# Firefly.net
KiCad netlist of a schematic drawn in EAGLE
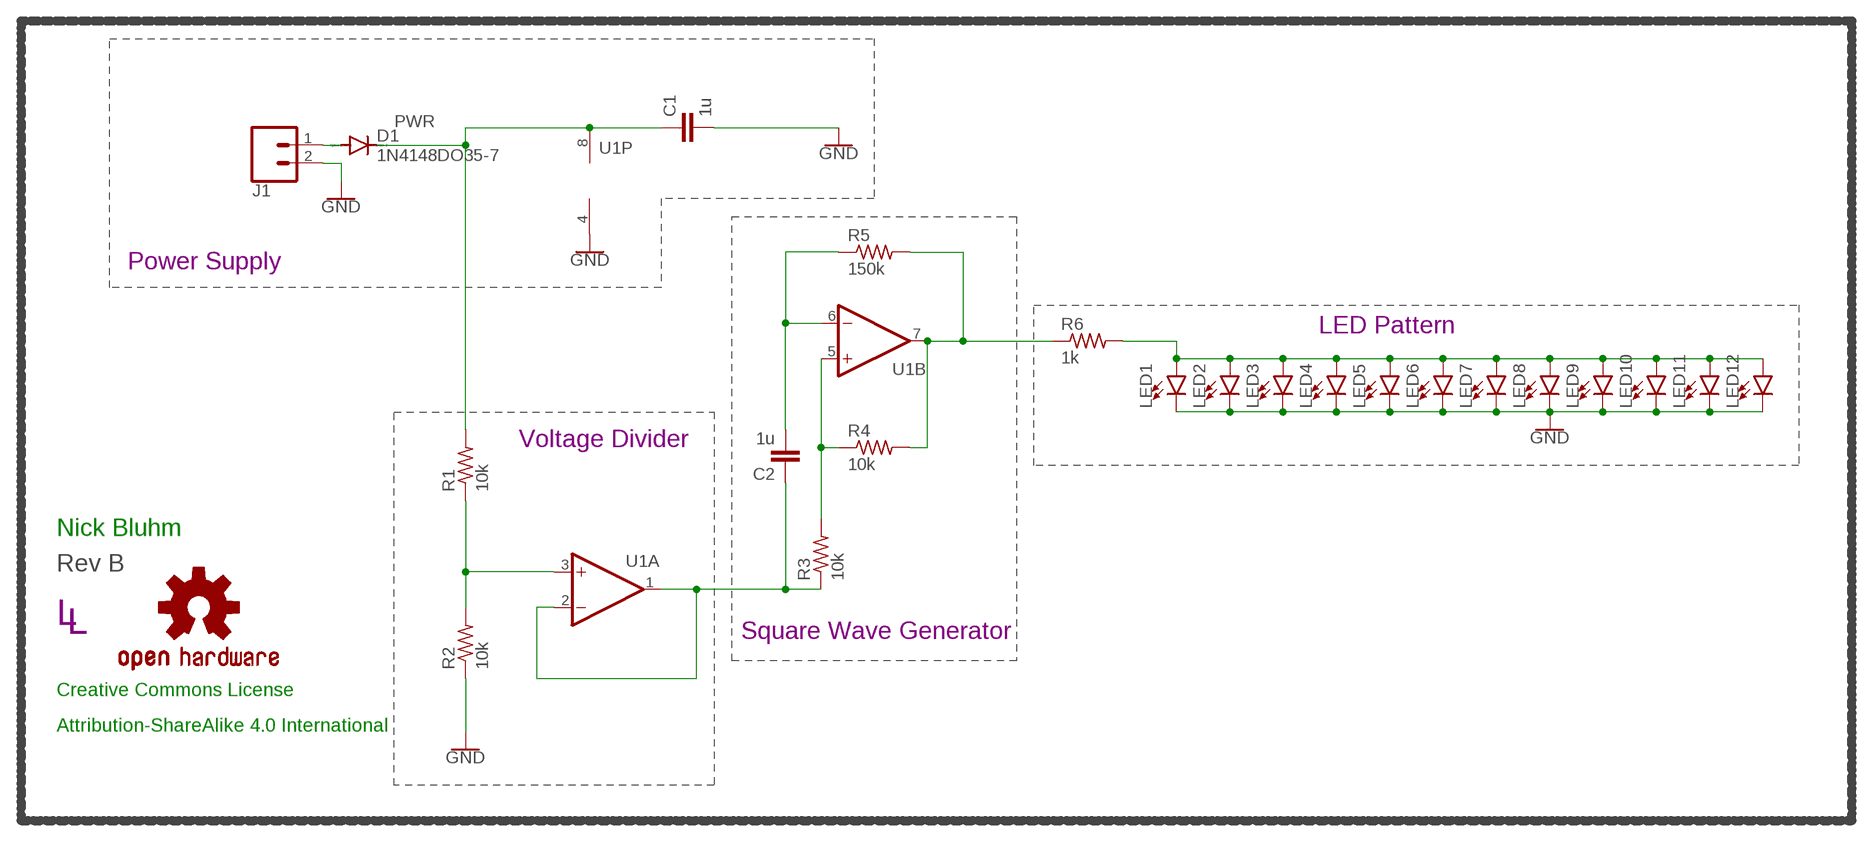
[diagram p0: schematic, sheet 1]

(export (version "E")
  (design (tool "Eeschema 10.0.6"))
  (components
    (comp (ref "C1")
      (value "1u")
      (footprint "eagle-import:C0805")
      (libsource (lib "eagle-import") (part "CAPACITOR0805"))
    )
    (comp (ref "C2")
      (value "1u")
      (footprint "eagle-import:C0805")
      (libsource (lib "eagle-import") (part "CAPACITOR0805"))
    )
    (comp (ref "D1")
      (value "1N4148DO35-7")
      (footprint "eagle-import:DO35-7")
      (libsource (lib "eagle-import") (part "1N4148DO35-7"))
    )
    (comp (ref "J1")
      (value "CONN_02")
      (footprint "eagle-import:1X02")
      (libsource (lib "eagle-import") (part "CONN_02"))
    )
    (comp (ref "LED1")
      (value "LED5MM")
      (footprint "eagle-import:LED_5MM")
      (libsource (lib "eagle-import") (part "LED5MM"))
    )
    (comp (ref "LED2")
      (value "LED5MM")
      (footprint "eagle-import:LED_5MM")
      (libsource (lib "eagle-import") (part "LED5MM"))
    )
    (comp (ref "LED3")
      (value "LED5MM")
      (footprint "eagle-import:LED_5MM")
      (libsource (lib "eagle-import") (part "LED5MM"))
    )
    (comp (ref "LED4")
      (value "LED5MM")
      (footprint "eagle-import:LED_5MM")
      (libsource (lib "eagle-import") (part "LED5MM"))
    )
    (comp (ref "LED5")
      (value "LED5MM")
      (footprint "eagle-import:LED_5MM")
      (libsource (lib "eagle-import") (part "LED5MM"))
    )
    (comp (ref "LED6")
      (value "LED5MM")
      (footprint "eagle-import:LED_5MM")
      (libsource (lib "eagle-import") (part "LED5MM"))
    )
    (comp (ref "LED7")
      (value "LED5MM")
      (footprint "eagle-import:LED_5MM")
      (libsource (lib "eagle-import") (part "LED5MM"))
    )
    (comp (ref "LED8")
      (value "LED5MM")
      (footprint "eagle-import:LED_5MM")
      (libsource (lib "eagle-import") (part "LED5MM"))
    )
    (comp (ref "LED9")
      (value "LED5MM")
      (footprint "eagle-import:LED_5MM")
      (libsource (lib "eagle-import") (part "LED5MM"))
    )
    (comp (ref "LED10")
      (value "LED5MM")
      (footprint "eagle-import:LED_5MM")
      (libsource (lib "eagle-import") (part "LED5MM"))
    )
    (comp (ref "LED11")
      (value "LED5MM")
      (footprint "eagle-import:LED_5MM")
      (libsource (lib "eagle-import") (part "LED5MM"))
    )
    (comp (ref "LED12")
      (value "LED5MM")
      (footprint "eagle-import:LED_5MM")
      (libsource (lib "eagle-import") (part "LED5MM"))
    )
    (comp (ref "LOGO1")
      (value "OSHW-LOGOL")
      (footprint "eagle-import:OSHW-LOGO-L")
      (libsource (lib "eagle-import") (part "OSHW-LOGOL"))
    )
    (comp (ref "R1")
      (value "10k")
      (footprint "eagle-import:R0805")
      (libsource (lib "eagle-import") (part "RESISTOR0805"))
    )
    (comp (ref "R2")
      (value "10k")
      (footprint "eagle-import:R0805")
      (libsource (lib "eagle-import") (part "RESISTOR0805"))
    )
    (comp (ref "R3")
      (value "10k")
      (footprint "eagle-import:R0805")
      (libsource (lib "eagle-import") (part "RESISTOR0805"))
    )
    (comp (ref "R4")
      (value "10k")
      (footprint "eagle-import:R0805")
      (libsource (lib "eagle-import") (part "RESISTOR0805"))
    )
    (comp (ref "R5")
      (value "150k")
      (footprint "eagle-import:R0805")
      (libsource (lib "eagle-import") (part "RESISTOR0805"))
    )
    (comp (ref "R6")
      (value "1k")
      (footprint "eagle-import:R0805")
      (libsource (lib "eagle-import") (part "RESISTOR0805"))
    )
    (comp (ref "U$4")
      (value "REVISION.B")
      (footprint "eagle-import:REV.B")
      (libsource (lib "eagle-import") (part "REVISION.B"))
    )
    (comp (ref "U$5")
      (value "LINNES.LAB.LOGO")
      (footprint "eagle-import:LINNES.LAB.LOGO")
      (libsource (lib "eagle-import") (part "LINNES.LAB.LOGO"))
    )
    (comp (ref "U1")
      (value "OP-DUALMCP6002R")
      (footprint "eagle-import:SO8")
      (fields (field (name "MF") "Microchip Technology") (field (name "MPN") "MCP6002T-I/SN"))
      (libsource (lib "eagle-import") (part "OP-DUALRMCP6002"))
    )
  )
  (nets
    (net (code "1") (name "/PWR") (class "Default")
      (node (ref "C1") (pin "1") (pinfunction "1_1") (pintype "passive"))
      (node (ref "D1") (pin "C") (pinfunction "C_C") (pintype "passive"))
      (node (ref "R1") (pin "2") (pinfunction "2_2") (pintype "passive"))
      (node (ref "U1") (pin "8") (pinfunction "V+_8") (pintype "power_in"))
    )
    (net (code "2") (name "GND") (class "Default")
      (node (ref "C1") (pin "2") (pinfunction "2_2") (pintype "passive"))
      (node (ref "J1") (pin "2") (pinfunction "2_2") (pintype "passive"))
      (node (ref "LED1") (pin "K") (pinfunction "C_K") (pintype "passive"))
      (node (ref "LED10") (pin "K") (pinfunction "C_K") (pintype "passive"))
      (node (ref "LED11") (pin "K") (pinfunction "C_K") (pintype "passive"))
      (node (ref "LED12") (pin "K") (pinfunction "C_K") (pintype "passive"))
      (node (ref "LED2") (pin "K") (pinfunction "C_K") (pintype "passive"))
      (node (ref "LED3") (pin "K") (pinfunction "C_K") (pintype "passive"))
      (node (ref "LED4") (pin "K") (pinfunction "C_K") (pintype "passive"))
      (node (ref "LED5") (pin "K") (pinfunction "C_K") (pintype "passive"))
      (node (ref "LED6") (pin "K") (pinfunction "C_K") (pintype "passive"))
      (node (ref "LED7") (pin "K") (pinfunction "C_K") (pintype "passive"))
      (node (ref "LED8") (pin "K") (pinfunction "C_K") (pintype "passive"))
      (node (ref "LED9") (pin "K") (pinfunction "C_K") (pintype "passive"))
      (node (ref "R2") (pin "1") (pinfunction "1_1") (pintype "passive"))
      (node (ref "U1") (pin "4") (pinfunction "V-_4") (pintype "power_in"))
    )
    (net (code "3") (name "Net-(D1-PadA)") (class "Default")
      (node (ref "D1") (pin "A") (pinfunction "A_A") (pintype "passive"))
      (node (ref "J1") (pin "1") (pinfunction "1_1") (pintype "passive"))
    )
    (net (code "4") (name "Net-(LED1-PadA)") (class "Default")
      (node (ref "LED1") (pin "A") (pinfunction "A_A") (pintype "passive"))
      (node (ref "LED10") (pin "A") (pinfunction "A_A") (pintype "passive"))
      (node (ref "LED11") (pin "A") (pinfunction "A_A") (pintype "passive"))
      (node (ref "LED12") (pin "A") (pinfunction "A_A") (pintype "passive"))
      (node (ref "LED2") (pin "A") (pinfunction "A_A") (pintype "passive"))
      (node (ref "LED3") (pin "A") (pinfunction "A_A") (pintype "passive"))
      (node (ref "LED4") (pin "A") (pinfunction "A_A") (pintype "passive"))
      (node (ref "LED5") (pin "A") (pinfunction "A_A") (pintype "passive"))
      (node (ref "LED6") (pin "A") (pinfunction "A_A") (pintype "passive"))
      (node (ref "LED7") (pin "A") (pinfunction "A_A") (pintype "passive"))
      (node (ref "LED8") (pin "A") (pinfunction "A_A") (pintype "passive"))
      (node (ref "LED9") (pin "A") (pinfunction "A_A") (pintype "passive"))
      (node (ref "R6") (pin "2") (pinfunction "2_2") (pintype "passive"))
    )
    (net (code "5") (name "Net-(U1A-+IN)") (class "Default")
      (node (ref "R1") (pin "1") (pinfunction "1_1") (pintype "passive"))
      (node (ref "R2") (pin "2") (pinfunction "2_2") (pintype "passive"))
      (node (ref "U1") (pin "3") (pinfunction "+IN_3") (pintype "input"))
    )
    (net (code "6") (name "Net-(U1A--IN)") (class "Default")
      (node (ref "C2") (pin "1") (pinfunction "1_1") (pintype "passive"))
      (node (ref "R3") (pin "1") (pinfunction "1_1") (pintype "passive"))
      (node (ref "U1") (pin "1") (pinfunction "OUT_1") (pintype "output"))
      (node (ref "U1") (pin "2") (pinfunction "-IN_2") (pintype "input"))
    )
    (net (code "7") (name "Net-(U1B-+IN)") (class "Default")
      (node (ref "R3") (pin "2") (pinfunction "2_2") (pintype "passive"))
      (node (ref "R4") (pin "1") (pinfunction "1_1") (pintype "passive"))
      (node (ref "U1") (pin "5") (pinfunction "+IN_5") (pintype "input"))
    )
    (net (code "8") (name "Net-(U1B--IN)") (class "Default")
      (node (ref "C2") (pin "2") (pinfunction "2_2") (pintype "passive"))
      (node (ref "R5") (pin "1") (pinfunction "1_1") (pintype "passive"))
      (node (ref "U1") (pin "6") (pinfunction "-IN_6") (pintype "input"))
    )
    (net (code "9") (name "Net-(U1B-OUT)") (class "Default")
      (node (ref "R4") (pin "2") (pinfunction "2_2") (pintype "passive"))
      (node (ref "R5") (pin "2") (pinfunction "2_2") (pintype "passive"))
      (node (ref "R6") (pin "1") (pinfunction "1_1") (pintype "passive"))
      (node (ref "U1") (pin "7") (pinfunction "OUT_7") (pintype "output"))
    )
  )
)
